# CloudKon_WifiRelay.net
KiCad netlist of a schematic drawn in Altium Designer
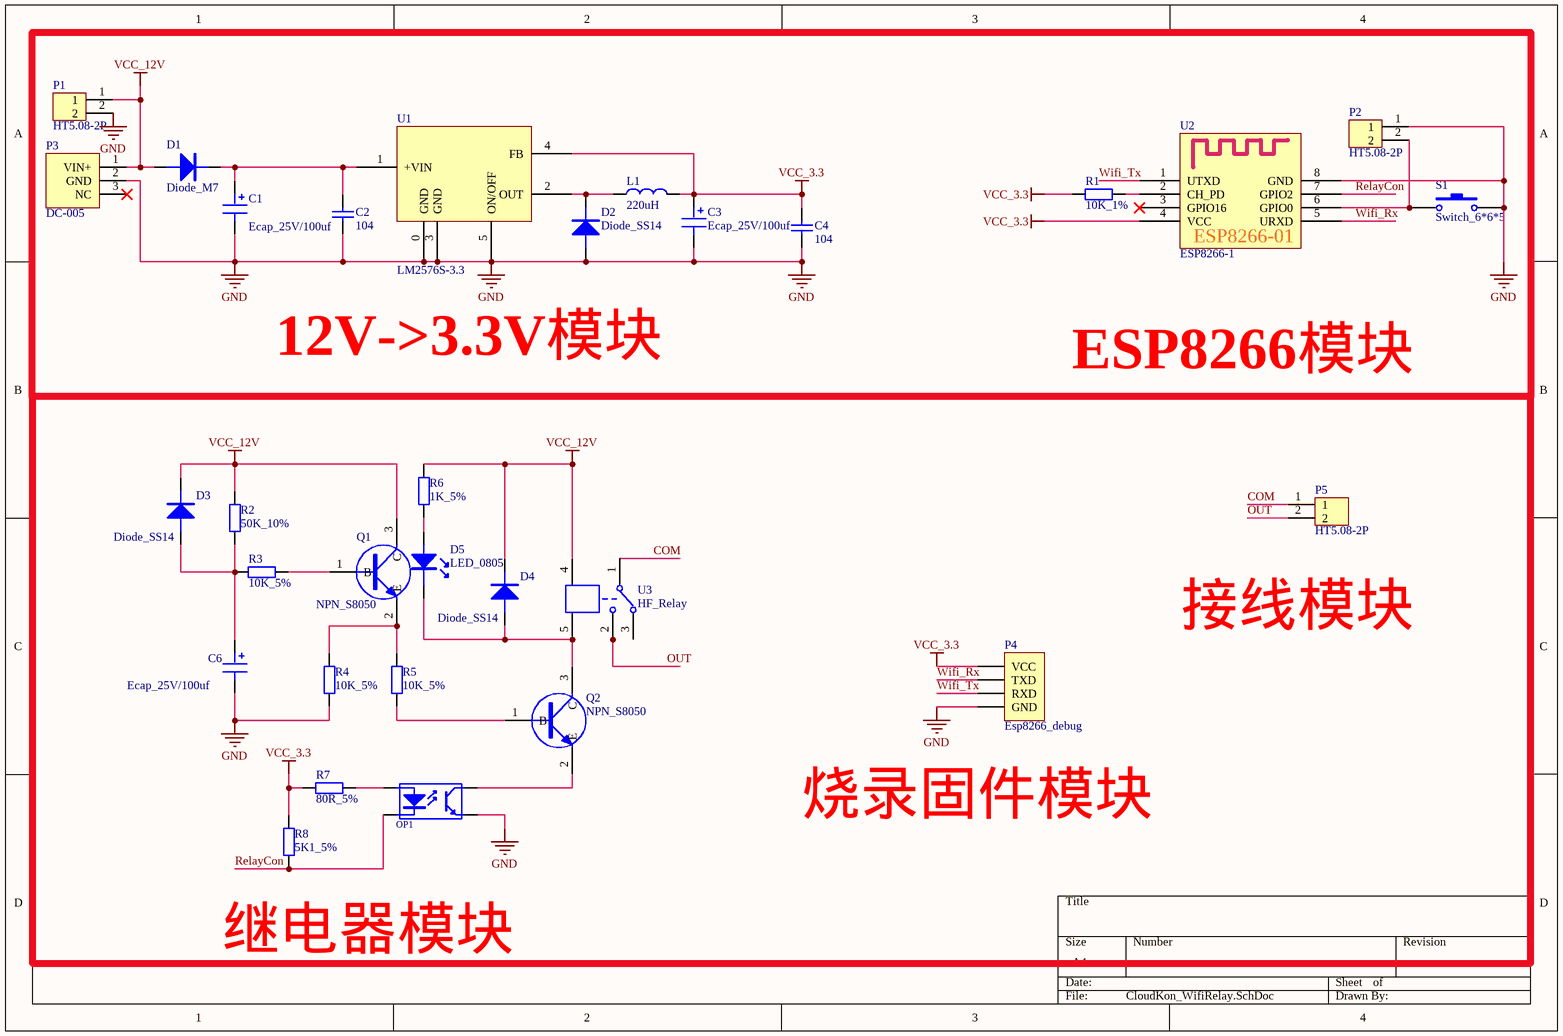
[diagram p0: CloudKon_WifiRelay.SchDoc]

(export (version "E")
  (design (tool "Eeschema 10.0.6"))
  (components
    (comp (ref "C1")
      (value "Ecap_25V/100uf")
      (footprint "sip-cap-100uf-25v - duplicate")
      (description "https://item.taobao.com/item.htm?spm=a1z10.5-c.w4002-11020631983.33.qoX6of&id=7423722992")
      (libsource (lib "NortCele_SchLib") (part "Ecap_25V/100uf"))
    )
    (comp (ref "C2")
      (value "104")
      (footprint "0805_Cap")
      (description "https://item.taobao.com/item.htm?spm=a1z09.2.0.0.hNveX1&id=9716419590&_u=7ok62qs2673")
      (libsource (lib "NortCele_SchLib") (part "Cap_%10"))
    )
    (comp (ref "C3")
      (value "Ecap_25V/100uf")
      (footprint "sip-cap-100uf-25v - duplicate")
      (description "https://item.taobao.com/item.htm?spm=a1z10.5-c.w4002-11020631983.33.qoX6of&id=7423722992")
      (libsource (lib "NortCele_SchLib") (part "Ecap_25V/100uf"))
    )
    (comp (ref "C4")
      (value "104")
      (footprint "0805_Cap")
      (description "https://item.taobao.com/item.htm?spm=a1z09.2.0.0.hNveX1&id=9716419590&_u=7ok62qs2673")
      (libsource (lib "NortCele_SchLib") (part "Cap_%10"))
    )
    (comp (ref "C6")
      (value "Ecap_25V/100uf")
      (footprint "sip-cap-100uf-25v - duplicate")
      (description "https://item.taobao.com/item.htm?spm=a1z10.5-c.w4002-11020631983.33.qoX6of&id=7423722992")
      (libsource (lib "NortCele_SchLib") (part "Ecap_25V/100uf"))
    )
    (comp (ref "D1")
      (value "Diode_M7")
      (footprint "M7")
      (description "https://item.taobao.com/item.htm?spm=a1z10.3-c.w4002-11020657456.37.E0r8Bv&id=2891923922")
      (libsource (lib "NortCele_SchLib") (part "Diode_M7"))
    )
    (comp (ref "D2")
      (value "Diode_SS14")
      (footprint "M7")
      (description "https://item.taobao.com/item.htm?spm=a1z10.3-c.w4002-11020657456.14.qD67rq&id=6126767310")
      (libsource (lib "NortCele_SchLib") (part "Diode_SS14"))
    )
    (comp (ref "D3")
      (value "Diode_SS14")
      (footprint "M7")
      (description "https://item.taobao.com/item.htm?spm=a1z10.3-c.w4002-11020657456.14.qD67rq&id=6126767310")
      (libsource (lib "NortCele_SchLib") (part "Diode_SS14"))
    )
    (comp (ref "D4")
      (value "Diode_SS14")
      (footprint "M7")
      (description "https://item.taobao.com/item.htm?spm=a1z10.3-c.w4002-11020657456.14.qD67rq&id=6126767310")
      (libsource (lib "NortCele_SchLib") (part "Diode_SS14"))
    )
    (comp (ref "D5")
      (value "LED_0805")
      (footprint "0805_LED")
      (description "https://item.taobao.com/item.htm?spm=a1z10.3-c.w4002-11020657456.51.Ytz1qg&id=5169670346")
      (libsource (lib "NortCele_SchLib") (part "LED_0805"))
    )
    (comp (ref "L1")
      (value "220uH")
      (footprint "LL_1A")
      (description "https://item.taobao.com/item.htm?spm=a1z10.3-c.w4002-11020657456.14.KHn9vQ&id=8986036232")
      (libsource (lib "NortCele_SchLib") (part "LL_220uH"))
    )
    (comp (ref "OP1")
      (value "EL817")
      (footprint "E817-SMD")
      (description "https://item.taobao.com/item.htm?spm=a1z10.3-c.w4002-11020657456.9.xiQJya&id=9840822052")
      (libsource (lib "NortCele_SchLib") (part "EL817"))
    )
    (comp (ref "P1")
      (value "HT5.08-2P")
      (footprint "sip2")
      (description "https://item.taobao.com/item.htm?spm=a1z10.3-c.w4002-11020657456.22.46QWsT&id=19327735027")
      (libsource (lib "NortCele_SchLib") (part "HT5.08-2P"))
    )
    (comp (ref "P2")
      (value "HT5.08-2P")
      (footprint "sip2")
      (description "https://item.taobao.com/item.htm?spm=a1z10.3-c.w4002-11020657456.22.46QWsT&id=19327735027")
      (libsource (lib "NortCele_SchLib") (part "HT5.08-2P"))
    )
    (comp (ref "P3")
      (value "DC-005")
      (footprint "DC-5.5-2.1mm")
      (description "https://item.taobao.com/item.htm?spm=a1z10.3-c.w4002-11020657456.12.3OzBHB&id=5709638982")
      (libsource (lib "NortCele_SchLib") (part "DC-005"))
    )
    (comp (ref "P4")
      (value "Esp8266_debug")
      (footprint "sip4")
      (description "https://item.taobao.com/item.htm?spm=a1z10.3-c.w4002-11020657456.14.NtUqGh&id=6097555742")
      (libsource (lib "NortCele_SchLib") (part "Esp8266_debug"))
    )
    (comp (ref "P5")
      (value "HT5.08-2P")
      (footprint "HP2PA-5.08")
      (description "https://item.taobao.com/item.htm?spm=a1z10.3-c.w4002-11020657456.22.46QWsT&id=19327735027")
      (libsource (lib "") (part "HT5.08-2P_1"))
    )
    (comp (ref "Q1")
      (value "NPN_S8050")
      (footprint "SOT-23")
      (description "https://item.taobao.com/item.htm?spm=a1z10.3-c.w4002-11020657456.15.ysrU5Y&id=5957247576")
      (libsource (lib "NortCele_SchLib") (part "NPN_S8050"))
    )
    (comp (ref "Q2")
      (value "NPN_S8050")
      (footprint "SOT-23")
      (description "https://item.taobao.com/item.htm?spm=a1z10.3-c.w4002-11020657456.15.ysrU5Y&id=5957247576")
      (libsource (lib "NortCele_SchLib") (part "NPN_S8050"))
    )
    (comp (ref "R1")
      (value "10K_1%")
      (footprint "0805_Res")
      (description "https://item.taobao.com/item.htm?spm=a1z10.3-c.w4002-11020657456.13.233szV&id=14686636311")
      (libsource (lib "") (part "Res_%5_3"))
    )
    (comp (ref "R2")
      (value "50K_10%")
      (footprint "0805_Res")
      (description "https://item.taobao.com/item.htm?spm=a1z10.3-c.w4002-11020657456.13.233szV&id=14686636311")
      (libsource (lib "NortCele_SchLib") (part "Res_%5"))
    )
    (comp (ref "R3")
      (value "10K_5%")
      (footprint "0805_Res")
      (description "https://item.taobao.com/item.htm?spm=a1z10.3-c.w4002-11020657456.13.233szV&id=14686636311")
      (libsource (lib "") (part "Res_%5_2"))
    )
    (comp (ref "R4")
      (value "10K_5%")
      (footprint "0805_Res")
      (description "https://item.taobao.com/item.htm?spm=a1z10.3-c.w4002-11020657456.13.233szV&id=14686636311")
      (libsource (lib "NortCele_SchLib") (part "Res_%5"))
    )
    (comp (ref "R5")
      (value "10K_5%")
      (footprint "0805_Res")
      (description "https://item.taobao.com/item.htm?spm=a1z10.3-c.w4002-11020657456.13.233szV&id=14686636311")
      (libsource (lib "") (part "Res_%5_1"))
    )
    (comp (ref "R6")
      (value "1K_5%")
      (footprint "0805_Res")
      (description "https://item.taobao.com/item.htm?spm=a1z10.3-c.w4002-11020657456.13.233szV&id=14686636311")
      (libsource (lib "") (part "Res_%5_1"))
    )
    (comp (ref "R7")
      (value "80R_5%")
      (footprint "0805_Res")
      (description "https://item.taobao.com/item.htm?spm=a1z10.3-c.w4002-11020657456.13.233szV&id=14686636311")
      (libsource (lib "") (part "Res_%5_2"))
    )
    (comp (ref "R8")
      (value "5K1_5%")
      (footprint "0805_Res")
      (description "https://item.taobao.com/item.htm?spm=a1z10.3-c.w4002-11020657456.13.233szV&id=14686636311")
      (libsource (lib "") (part "Res_%5_1"))
    )
    (comp (ref "S1")
      (value "Switch_6*6*5")
      (footprint "4.5*4.5MM_SW")
      (description "https://item.taobao.com/item.htm?spm=a1z10.3-c.w4002-11020657456.46.btOzYB&id=6756135544")
      (libsource (lib "NortCele_SchLib") (part "Switch_6*6*5"))
    )
    (comp (ref "U1")
      (value "LM2576S-3.3")
      (footprint "LM2575-1")
      (description "https://item.taobao.com/item.htm?spm=a1z10.3-c.w4002-11020657456.21.xl3HJG&id=6674225198")
      (libsource (lib "NortCele_SchLib") (part "LM2576S-3.3"))
    )
    (comp (ref "U2")
      (value "ESP8266-1")
      (footprint "ESP8266-1")
      (description "https://item.taobao.com/item.htm?spm=a1z10.3-c.w4002-5350375195.29.OjbIzM&id=40328222213")
      (libsource (lib "NortCele_SchLib") (part "ESP8266-1"))
    )
    (comp (ref "U3")
      (value "HF_Relay")
      (footprint "JZ-32F-A")
      (description "https://item.taobao.com/item.htm?spm=a1z10.1-c.w9983160-11020631947.1.6Rxoz9&id=10387236348")
      (libsource (lib "NortCele_SchLib") (part "HF_Relay"))
    )
  )
  (nets
    (net (code "1") (name "/COM") (class "Default")
      (node (ref "P5") (pin "1") (pinfunction "1_1") (pintype "passive"))
      (node (ref "U3") (pin "1") (pinfunction "1_1") (pintype "passive"))
    )
    (net (code "2") (name "/OUT") (class "Default")
      (node (ref "P5") (pin "2") (pinfunction "2_2") (pintype "passive"))
      (node (ref "U3") (pin "2") (pinfunction "2_2") (pintype "passive"))
    )
    (net (code "3") (name "/RelayCon") (class "Default")
      (node (ref "OP1") (pin "2") (pinfunction "K_2") (pintype "passive"))
      (node (ref "R8") (pin "1") (pinfunction "1_1") (pintype "passive"))
      (node (ref "U2") (pin "7") (pinfunction "GPIO2_7") (pintype "passive"))
    )
    (net (code "4") (name "/Wifi_Rx") (class "Default")
      (node (ref "P4") (pin "2") (pinfunction "TXD_2") (pintype "passive"))
      (node (ref "U2") (pin "5") (pinfunction "URXD_5") (pintype "passive"))
    )
    (net (code "5") (name "/Wifi_Tx") (class "Default")
      (node (ref "P4") (pin "3") (pinfunction "RXD_3") (pintype "passive"))
      (node (ref "U2") (pin "1") (pinfunction "UTXD_1") (pintype "passive"))
    )
    (net (code "6") (name "GND") (class "Default")
      (node (ref "C1") (pin "2") (pinfunction "2_2") (pintype "passive"))
      (node (ref "C2") (pin "1") (pinfunction "1_1") (pintype "passive"))
      (node (ref "C3") (pin "2") (pinfunction "2_2") (pintype "passive"))
      (node (ref "C4") (pin "1") (pinfunction "1_1") (pintype "passive"))
      (node (ref "C6") (pin "2") (pinfunction "2_2") (pintype "passive"))
      (node (ref "D2") (pin "A") (pinfunction "1_A") (pintype "passive"))
      (node (ref "OP1") (pin "3") (pinfunction "E_3") (pintype "passive"))
      (node (ref "P1") (pin "2") (pinfunction "2_2") (pintype "passive"))
      (node (ref "P2") (pin "1") (pinfunction "1_1") (pintype "passive"))
      (node (ref "P3") (pin "2") (pinfunction "GND_2") (pintype "passive"))
      (node (ref "P4") (pin "4") (pinfunction "GND_4") (pintype "passive"))
      (node (ref "R4") (pin "2") (pinfunction "2_2") (pintype "passive"))
      (node (ref "S1") (pin "2") (pinfunction "2_2") (pintype "passive"))
      (node (ref "U1") (pin "0") (pinfunction "GND_0") (pintype "passive"))
      (node (ref "U1") (pin "3") (pinfunction "GND_3") (pintype "passive"))
      (node (ref "U1") (pin "5") (pinfunction "ON/OFF_5") (pintype "passive"))
      (node (ref "U2") (pin "8") (pinfunction "GND_8") (pintype "passive"))
    )
    (net (code "7") (name "Net-(D1-2)") (class "Default")
      (node (ref "C1") (pin "1") (pinfunction "1_1") (pintype "passive"))
      (node (ref "C2") (pin "2") (pinfunction "2_2") (pintype "passive"))
      (node (ref "D1") (pin "K") (pinfunction "2_K") (pintype "passive"))
      (node (ref "U1") (pin "1") (pinfunction "+VIN_1") (pintype "passive"))
    )
    (net (code "8") (name "Net-(D2-2)") (class "Default")
      (node (ref "D2") (pin "K") (pinfunction "2_K") (pintype "passive"))
      (node (ref "L1") (pin "1") (pintype "passive"))
      (node (ref "U1") (pin "2") (pinfunction "OUT_2") (pintype "passive"))
    )
    (net (code "9") (name "Net-(D3-1)") (class "Default")
      (node (ref "C6") (pin "1") (pinfunction "1_1") (pintype "passive"))
      (node (ref "D3") (pin "A") (pinfunction "1_A") (pintype "passive"))
      (node (ref "R2") (pin "2") (pinfunction "2_2") (pintype "passive"))
      (node (ref "R3") (pin "1") (pinfunction "1_1") (pintype "passive"))
    )
    (net (code "10") (name "Net-(D4-1)") (class "Default")
      (node (ref "D4") (pin "A") (pinfunction "1_A") (pintype "passive"))
      (node (ref "D5") (pin "2") (pinfunction "2_2") (pintype "passive"))
      (node (ref "Q2") (pin "3") (pinfunction "C_3") (pintype "passive"))
      (node (ref "U3") (pin "5") (pinfunction "5_5") (pintype "passive"))
    )
    (net (code "11") (name "Net-(D5-Pad1)") (class "Default")
      (node (ref "D5") (pin "1") (pinfunction "1_1") (pintype "passive"))
      (node (ref "R6") (pin "1") (pinfunction "1_1") (pintype "passive"))
    )
    (net (code "12") (name "Net-(OP1-A)") (class "Default")
      (node (ref "OP1") (pin "1") (pinfunction "A_1") (pintype "passive"))
      (node (ref "R7") (pin "2") (pinfunction "2_2") (pintype "passive"))
    )
    (net (code "13") (name "Net-(OP1-C)") (class "Default")
      (node (ref "OP1") (pin "4") (pinfunction "C_4") (pintype "passive"))
      (node (ref "Q2") (pin "2") (pinfunction "E_2") (pintype "passive"))
    )
    (net (code "14") (name "Net-(Q1-B)") (class "Default")
      (node (ref "Q1") (pin "1") (pinfunction "B_1") (pintype "passive"))
      (node (ref "R3") (pin "2") (pinfunction "2_2") (pintype "passive"))
    )
    (net (code "15") (name "Net-(Q1-E)") (class "Default")
      (node (ref "Q1") (pin "2") (pinfunction "E_2") (pintype "passive"))
      (node (ref "R4") (pin "1") (pinfunction "1_1") (pintype "passive"))
      (node (ref "R5") (pin "2") (pinfunction "2_2") (pintype "passive"))
    )
    (net (code "16") (name "Net-(Q2-B)") (class "Default")
      (node (ref "Q2") (pin "1") (pinfunction "B_1") (pintype "passive"))
      (node (ref "R5") (pin "1") (pinfunction "1_1") (pintype "passive"))
    )
    (net (code "17") (name "Net-(U2-CH_PD)") (class "Default")
      (node (ref "R1") (pin "1") (pinfunction "1_1") (pintype "passive"))
      (node (ref "U2") (pin "2") (pinfunction "CH_PD_2") (pintype "passive"))
    )
    (net (code "18") (name "Net-(U2-GPIO0)") (class "Default")
      (node (ref "P2") (pin "2") (pinfunction "2_2") (pintype "passive"))
      (node (ref "S1") (pin "1") (pinfunction "1_1") (pintype "passive"))
      (node (ref "U2") (pin "6") (pinfunction "GPIO0_6") (pintype "passive"))
    )
    (net (code "19") (name "VCC_3.3") (class "Default")
      (node (ref "C3") (pin "1") (pinfunction "1_1") (pintype "passive"))
      (node (ref "C4") (pin "2") (pinfunction "2_2") (pintype "passive"))
      (node (ref "L1") (pin "2") (pintype "passive"))
      (node (ref "P4") (pin "1") (pinfunction "VCC_1") (pintype "passive"))
      (node (ref "R1") (pin "2") (pinfunction "2_2") (pintype "passive"))
      (node (ref "R7") (pin "1") (pinfunction "1_1") (pintype "passive"))
      (node (ref "R8") (pin "2") (pinfunction "2_2") (pintype "passive"))
      (node (ref "U1") (pin "4") (pinfunction "FB_4") (pintype "passive"))
      (node (ref "U2") (pin "4") (pinfunction "VCC_4") (pintype "passive"))
    )
    (net (code "20") (name "VCC_12V") (class "Default")
      (node (ref "D1") (pin "A") (pinfunction "1_A") (pintype "passive"))
      (node (ref "D3") (pin "K") (pinfunction "2_K") (pintype "passive"))
      (node (ref "D4") (pin "K") (pinfunction "2_K") (pintype "passive"))
      (node (ref "P1") (pin "1") (pinfunction "1_1") (pintype "passive"))
      (node (ref "P3") (pin "1") (pinfunction "VIN+_1") (pintype "passive"))
      (node (ref "Q1") (pin "3") (pinfunction "C_3") (pintype "passive"))
      (node (ref "R2") (pin "1") (pinfunction "1_1") (pintype "passive"))
      (node (ref "R6") (pin "2") (pinfunction "2_2") (pintype "passive"))
      (node (ref "U3") (pin "4") (pinfunction "4_4") (pintype "passive"))
    )
    (net (code "21") (name "unconnected-(P3-NC-Pad3)") (class "Default")
      (node (ref "P3") (pin "3") (pinfunction "NC_3") (pintype "passive+no_connect"))
    )
    (net (code "22") (name "unconnected-(U2-GPIO16-Pad3)") (class "Default")
      (node (ref "U2") (pin "3") (pinfunction "GPIO16_3") (pintype "passive+no_connect"))
    )
    (net (code "23") (name "unconnected-(U3-Pad3)") (class "Default")
      (node (ref "U3") (pin "3") (pinfunction "3_3") (pintype "passive"))
    )
  )
)
